# board.net
KiCad netlist of a schematic drawn in EAGLE
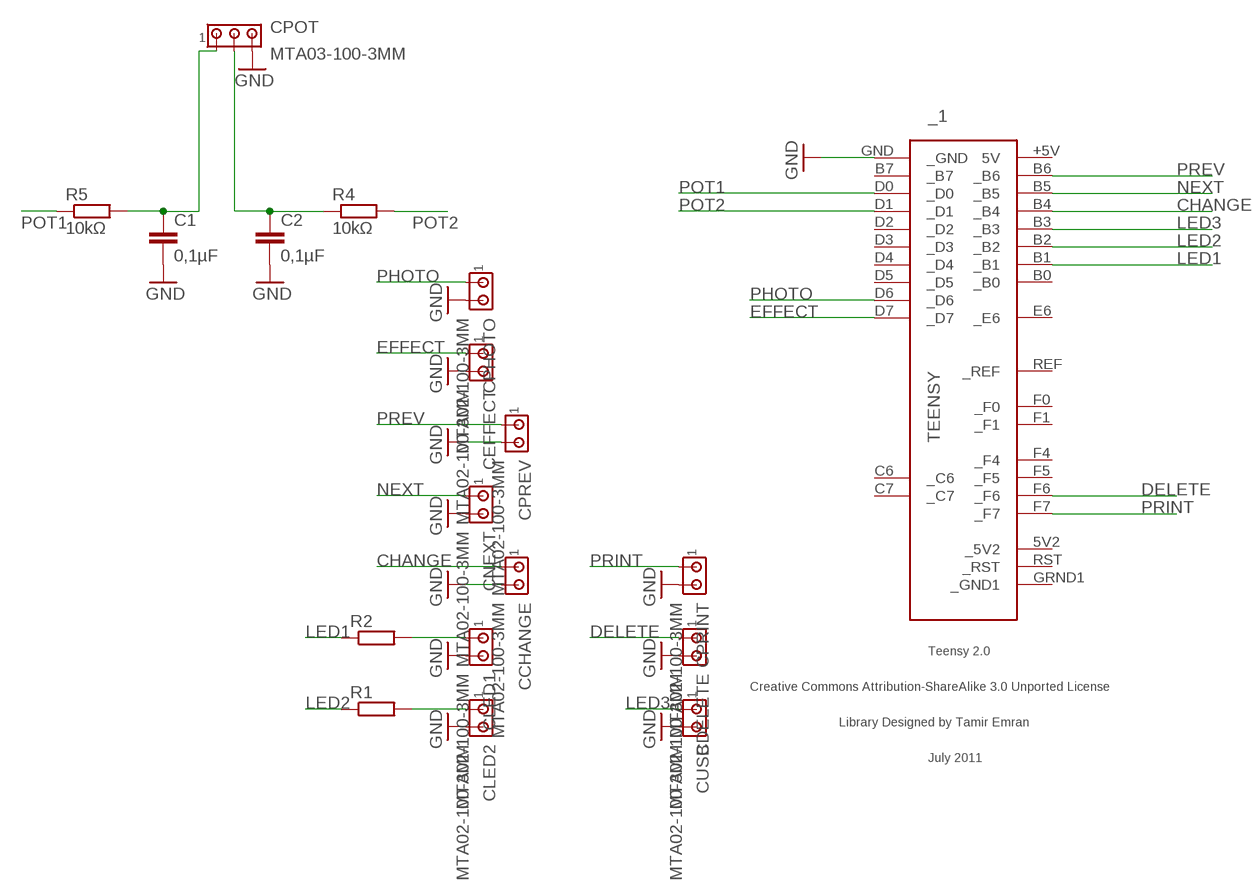
[diagram p0: schematic, sheet 1]

(export (version "E")
  (design (tool "Eeschema 10.0.6"))
  (components
    (comp (ref "C1")
      (value "0,1µF")
      (footprint "eagle-import:C050-025X075")
      (libsource (lib "eagle-import") (part "C-EU050-025X075"))
    )
    (comp (ref "C2")
      (value "0,1µF")
      (footprint "eagle-import:C050-025X075")
      (libsource (lib "eagle-import") (part "C-EU050-025X075"))
    )
    (comp (ref "CCHANGE")
      (value "MTA02-100-3MM")
      (footprint "eagle-import:10X02MTA3MM")
      (libsource (lib "eagle-import") (part "MTA02-100-3MM"))
    )
    (comp (ref "CDELETE")
      (value "MTA02-100-3MM")
      (footprint "eagle-import:10X02MTA3MM")
      (libsource (lib "eagle-import") (part "MTA02-100-3MM"))
    )
    (comp (ref "CEFFECT")
      (value "MTA02-100-3MM")
      (footprint "eagle-import:10X02MTA3MM")
      (libsource (lib "eagle-import") (part "MTA02-100-3MM"))
    )
    (comp (ref "CLED1")
      (value "MTA02-100-3MM")
      (footprint "eagle-import:10X02MTA3MM")
      (libsource (lib "eagle-import") (part "MTA02-100-3MM"))
    )
    (comp (ref "CLED2")
      (value "MTA02-100-3MM")
      (footprint "eagle-import:10X02MTA3MM")
      (libsource (lib "eagle-import") (part "MTA02-100-3MM"))
    )
    (comp (ref "CNEXT")
      (value "MTA02-100-3MM")
      (footprint "eagle-import:10X02MTA3MM")
      (libsource (lib "eagle-import") (part "MTA02-100-3MM"))
    )
    (comp (ref "CPHOTO")
      (value "MTA02-100-3MM")
      (footprint "eagle-import:10X02MTA3MM")
      (libsource (lib "eagle-import") (part "MTA02-100-3MM"))
    )
    (comp (ref "CPOT")
      (value "MTA03-100-3MM")
      (footprint "eagle-import:10X03MTA3MM")
      (libsource (lib "eagle-import") (part "MTA03-100-3MM"))
    )
    (comp (ref "CPREV")
      (value "MTA02-100-3MM")
      (footprint "eagle-import:10X02MTA3MM")
      (libsource (lib "eagle-import") (part "MTA02-100-3MM"))
    )
    (comp (ref "CPRINT")
      (value "MTA02-100-3MM")
      (footprint "eagle-import:10X02MTA3MM")
      (libsource (lib "eagle-import") (part "MTA02-100-3MM"))
    )
    (comp (ref "CUSB")
      (value "MTA02-100-3MM")
      (footprint "eagle-import:10X02MTA3MM")
      (libsource (lib "eagle-import") (part "MTA02-100-3MM"))
    )
    (comp (ref "R1")
      (value "R-EU_0204/5")
      (footprint "eagle-import:0204_5")
      (libsource (lib "eagle-import") (part "R-EU_0204/5"))
    )
    (comp (ref "R2")
      (value "R-EU_0204/5")
      (footprint "eagle-import:0204_5")
      (libsource (lib "eagle-import") (part "R-EU_0204/5"))
    )
    (comp (ref "R4")
      (value "10kΩ")
      (footprint "eagle-import:0207_7")
      (libsource (lib "eagle-import") (part "R-EU_0207/7"))
    )
    (comp (ref "R5")
      (value "10kΩ")
      (footprint "eagle-import:0207_7")
      (libsource (lib "eagle-import") (part "R-EU_0207/7"))
    )
    (comp (ref "_1")
      (value "TEENSY")
      (footprint "eagle-import:TEENSY")
      (libsource (lib "eagle-import") (part "TEENSY"))
    )
  )
  (nets
    (net (code "1") (name "/CHANGE") (class "Default")
      (node (ref "CCHANGE") (pin "1") (pinfunction "1_1") (pintype "passive"))
      (node (ref "_1") (pin "B4") (pinfunction "_B4_B4") (pintype "bidirectional"))
    )
    (net (code "2") (name "/DELETE") (class "Default")
      (node (ref "CDELETE") (pin "1") (pinfunction "1_1") (pintype "passive"))
      (node (ref "_1") (pin "F6") (pinfunction "_F6_F6") (pintype "bidirectional"))
    )
    (net (code "3") (name "/EFFECT") (class "Default")
      (node (ref "CEFFECT") (pin "1") (pinfunction "1_1") (pintype "passive"))
      (node (ref "_1") (pin "D7") (pinfunction "_D7_D7") (pintype "bidirectional"))
    )
    (net (code "4") (name "/LED1") (class "Default")
      (node (ref "R2") (pin "1") (pinfunction "1_1") (pintype "passive"))
      (node (ref "_1") (pin "B1") (pinfunction "_B1_B1") (pintype "bidirectional"))
    )
    (net (code "5") (name "/LED2") (class "Default")
      (node (ref "R1") (pin "1") (pinfunction "1_1") (pintype "passive"))
      (node (ref "_1") (pin "B2") (pinfunction "_B2_B2") (pintype "bidirectional"))
    )
    (net (code "6") (name "/LED3") (class "Default")
      (node (ref "CUSB") (pin "1") (pinfunction "1_1") (pintype "passive"))
      (node (ref "_1") (pin "B3") (pinfunction "_B3_B3") (pintype "bidirectional"))
    )
    (net (code "7") (name "/NEXT") (class "Default")
      (node (ref "CNEXT") (pin "1") (pinfunction "1_1") (pintype "passive"))
      (node (ref "_1") (pin "B5") (pinfunction "_B5_B5") (pintype "bidirectional"))
    )
    (net (code "8") (name "/PHOTO") (class "Default")
      (node (ref "CPHOTO") (pin "1") (pinfunction "1_1") (pintype "passive"))
      (node (ref "_1") (pin "D6") (pinfunction "_D6_D6") (pintype "bidirectional"))
    )
    (net (code "9") (name "/POT1") (class "Default")
      (node (ref "R5") (pin "1") (pinfunction "1_1") (pintype "passive"))
      (node (ref "_1") (pin "D0") (pinfunction "_D0_D0") (pintype "bidirectional"))
    )
    (net (code "10") (name "/POT2") (class "Default")
      (node (ref "R4") (pin "2") (pinfunction "2_2") (pintype "passive"))
      (node (ref "_1") (pin "D1") (pinfunction "_D1_D1") (pintype "bidirectional"))
    )
    (net (code "11") (name "/PREV") (class "Default")
      (node (ref "CPREV") (pin "1") (pinfunction "1_1") (pintype "passive"))
      (node (ref "_1") (pin "B6") (pinfunction "_B6_B6") (pintype "bidirectional"))
    )
    (net (code "12") (name "/PRINT") (class "Default")
      (node (ref "CPRINT") (pin "1") (pinfunction "1_1") (pintype "passive"))
      (node (ref "_1") (pin "F7") (pinfunction "_F7_F7") (pintype "bidirectional"))
    )
    (net (code "13") (name "GND") (class "Default")
      (node (ref "C1") (pin "2") (pinfunction "2_2") (pintype "passive"))
      (node (ref "C2") (pin "2") (pinfunction "2_2") (pintype "passive"))
      (node (ref "CCHANGE") (pin "2") (pinfunction "2_2") (pintype "passive"))
      (node (ref "CDELETE") (pin "2") (pinfunction "2_2") (pintype "passive"))
      (node (ref "CEFFECT") (pin "2") (pinfunction "2_2") (pintype "passive"))
      (node (ref "CLED1") (pin "2") (pinfunction "2_2") (pintype "passive"))
      (node (ref "CLED2") (pin "2") (pinfunction "2_2") (pintype "passive"))
      (node (ref "CNEXT") (pin "2") (pinfunction "2_2") (pintype "passive"))
      (node (ref "CPHOTO") (pin "2") (pinfunction "2_2") (pintype "passive"))
      (node (ref "CPOT") (pin "3") (pinfunction "3_3") (pintype "passive"))
      (node (ref "CPREV") (pin "2") (pinfunction "2_2") (pintype "passive"))
      (node (ref "CPRINT") (pin "2") (pinfunction "2_2") (pintype "passive"))
      (node (ref "CUSB") (pin "2") (pinfunction "2_2") (pintype "passive"))
      (node (ref "_1") (pin "GND") (pinfunction "_GND_GND") (pintype "bidirectional"))
    )
    (net (code "14") (name "Net-(C1-Pad1)") (class "Default")
      (node (ref "C1") (pin "1") (pinfunction "1_1") (pintype "passive"))
      (node (ref "CPOT") (pin "1") (pinfunction "1_1") (pintype "passive"))
      (node (ref "R5") (pin "2") (pinfunction "2_2") (pintype "passive"))
    )
    (net (code "15") (name "Net-(C2-Pad1)") (class "Default")
      (node (ref "C2") (pin "1") (pinfunction "1_1") (pintype "passive"))
      (node (ref "CPOT") (pin "2") (pinfunction "2_2") (pintype "passive"))
      (node (ref "R4") (pin "1") (pinfunction "1_1") (pintype "passive"))
    )
    (net (code "16") (name "Net-(CLED1-Pad1)") (class "Default")
      (node (ref "CLED1") (pin "1") (pinfunction "1_1") (pintype "passive"))
      (node (ref "R2") (pin "2") (pinfunction "2_2") (pintype "passive"))
    )
    (net (code "17") (name "Net-(CLED2-Pad1)") (class "Default")
      (node (ref "CLED2") (pin "1") (pinfunction "1_1") (pintype "passive"))
      (node (ref "R1") (pin "2") (pinfunction "2_2") (pintype "passive"))
    )
    (net (code "18") (name "unconnected-(_1-5V-Pad+5V)") (class "Default")
      (node (ref "_1") (pin "+5V") (pinfunction "5V_+5V") (pintype "bidirectional"))
    )
    (net (code "19") (name "unconnected-(_1-_5V2-Pad5V2)") (class "Default")
      (node (ref "_1") (pin "5V2") (pinfunction "_5V2_5V2") (pintype "bidirectional"))
    )
    (net (code "20") (name "unconnected-(_1-_B0-PadB0)") (class "Default")
      (node (ref "_1") (pin "B0") (pinfunction "_B0_B0") (pintype "bidirectional"))
    )
    (net (code "21") (name "unconnected-(_1-_B7-PadB7)") (class "Default")
      (node (ref "_1") (pin "B7") (pinfunction "_B7_B7") (pintype "bidirectional"))
    )
    (net (code "22") (name "unconnected-(_1-_C6-PadC6)") (class "Default")
      (node (ref "_1") (pin "C6") (pinfunction "_C6_C6") (pintype "bidirectional"))
    )
    (net (code "23") (name "unconnected-(_1-_C7-PadC7)") (class "Default")
      (node (ref "_1") (pin "C7") (pinfunction "_C7_C7") (pintype "bidirectional"))
    )
    (net (code "24") (name "unconnected-(_1-_D2-PadD2)") (class "Default")
      (node (ref "_1") (pin "D2") (pinfunction "_D2_D2") (pintype "bidirectional"))
    )
    (net (code "25") (name "unconnected-(_1-_D3-PadD3)") (class "Default")
      (node (ref "_1") (pin "D3") (pinfunction "_D3_D3") (pintype "bidirectional"))
    )
    (net (code "26") (name "unconnected-(_1-_D4-PadD4)") (class "Default")
      (node (ref "_1") (pin "D4") (pinfunction "_D4_D4") (pintype "bidirectional"))
    )
    (net (code "27") (name "unconnected-(_1-_D5-PadD5)") (class "Default")
      (node (ref "_1") (pin "D5") (pinfunction "_D5_D5") (pintype "bidirectional"))
    )
    (net (code "28") (name "unconnected-(_1-_E6-PadE6)") (class "Default")
      (node (ref "_1") (pin "E6") (pinfunction "_E6_E6") (pintype "bidirectional"))
    )
    (net (code "29") (name "unconnected-(_1-_F0-PadF0)") (class "Default")
      (node (ref "_1") (pin "F0") (pinfunction "_F0_F0") (pintype "bidirectional"))
    )
    (net (code "30") (name "unconnected-(_1-_F1-PadF1)") (class "Default")
      (node (ref "_1") (pin "F1") (pinfunction "_F1_F1") (pintype "bidirectional"))
    )
    (net (code "31") (name "unconnected-(_1-_F4-PadF4)") (class "Default")
      (node (ref "_1") (pin "F4") (pinfunction "_F4_F4") (pintype "bidirectional"))
    )
    (net (code "32") (name "unconnected-(_1-_F5-PadF5)") (class "Default")
      (node (ref "_1") (pin "F5") (pinfunction "_F5_F5") (pintype "bidirectional"))
    )
    (net (code "33") (name "unconnected-(_1-_GND1-PadGRND1)") (class "Default")
      (node (ref "_1") (pin "GRND1") (pinfunction "_GND1_GRND1") (pintype "bidirectional"))
    )
    (net (code "34") (name "unconnected-(_1-_REF-PadREF)") (class "Default")
      (node (ref "_1") (pin "REF") (pinfunction "_REF_REF") (pintype "bidirectional"))
    )
    (net (code "35") (name "unconnected-(_1-_RST-PadRST)") (class "Default")
      (node (ref "_1") (pin "RST") (pinfunction "_RST_RST") (pintype "bidirectional"))
    )
  )
)
